# reflow_controller_v2.net
KiCad netlist of a schematic drawn in EAGLE
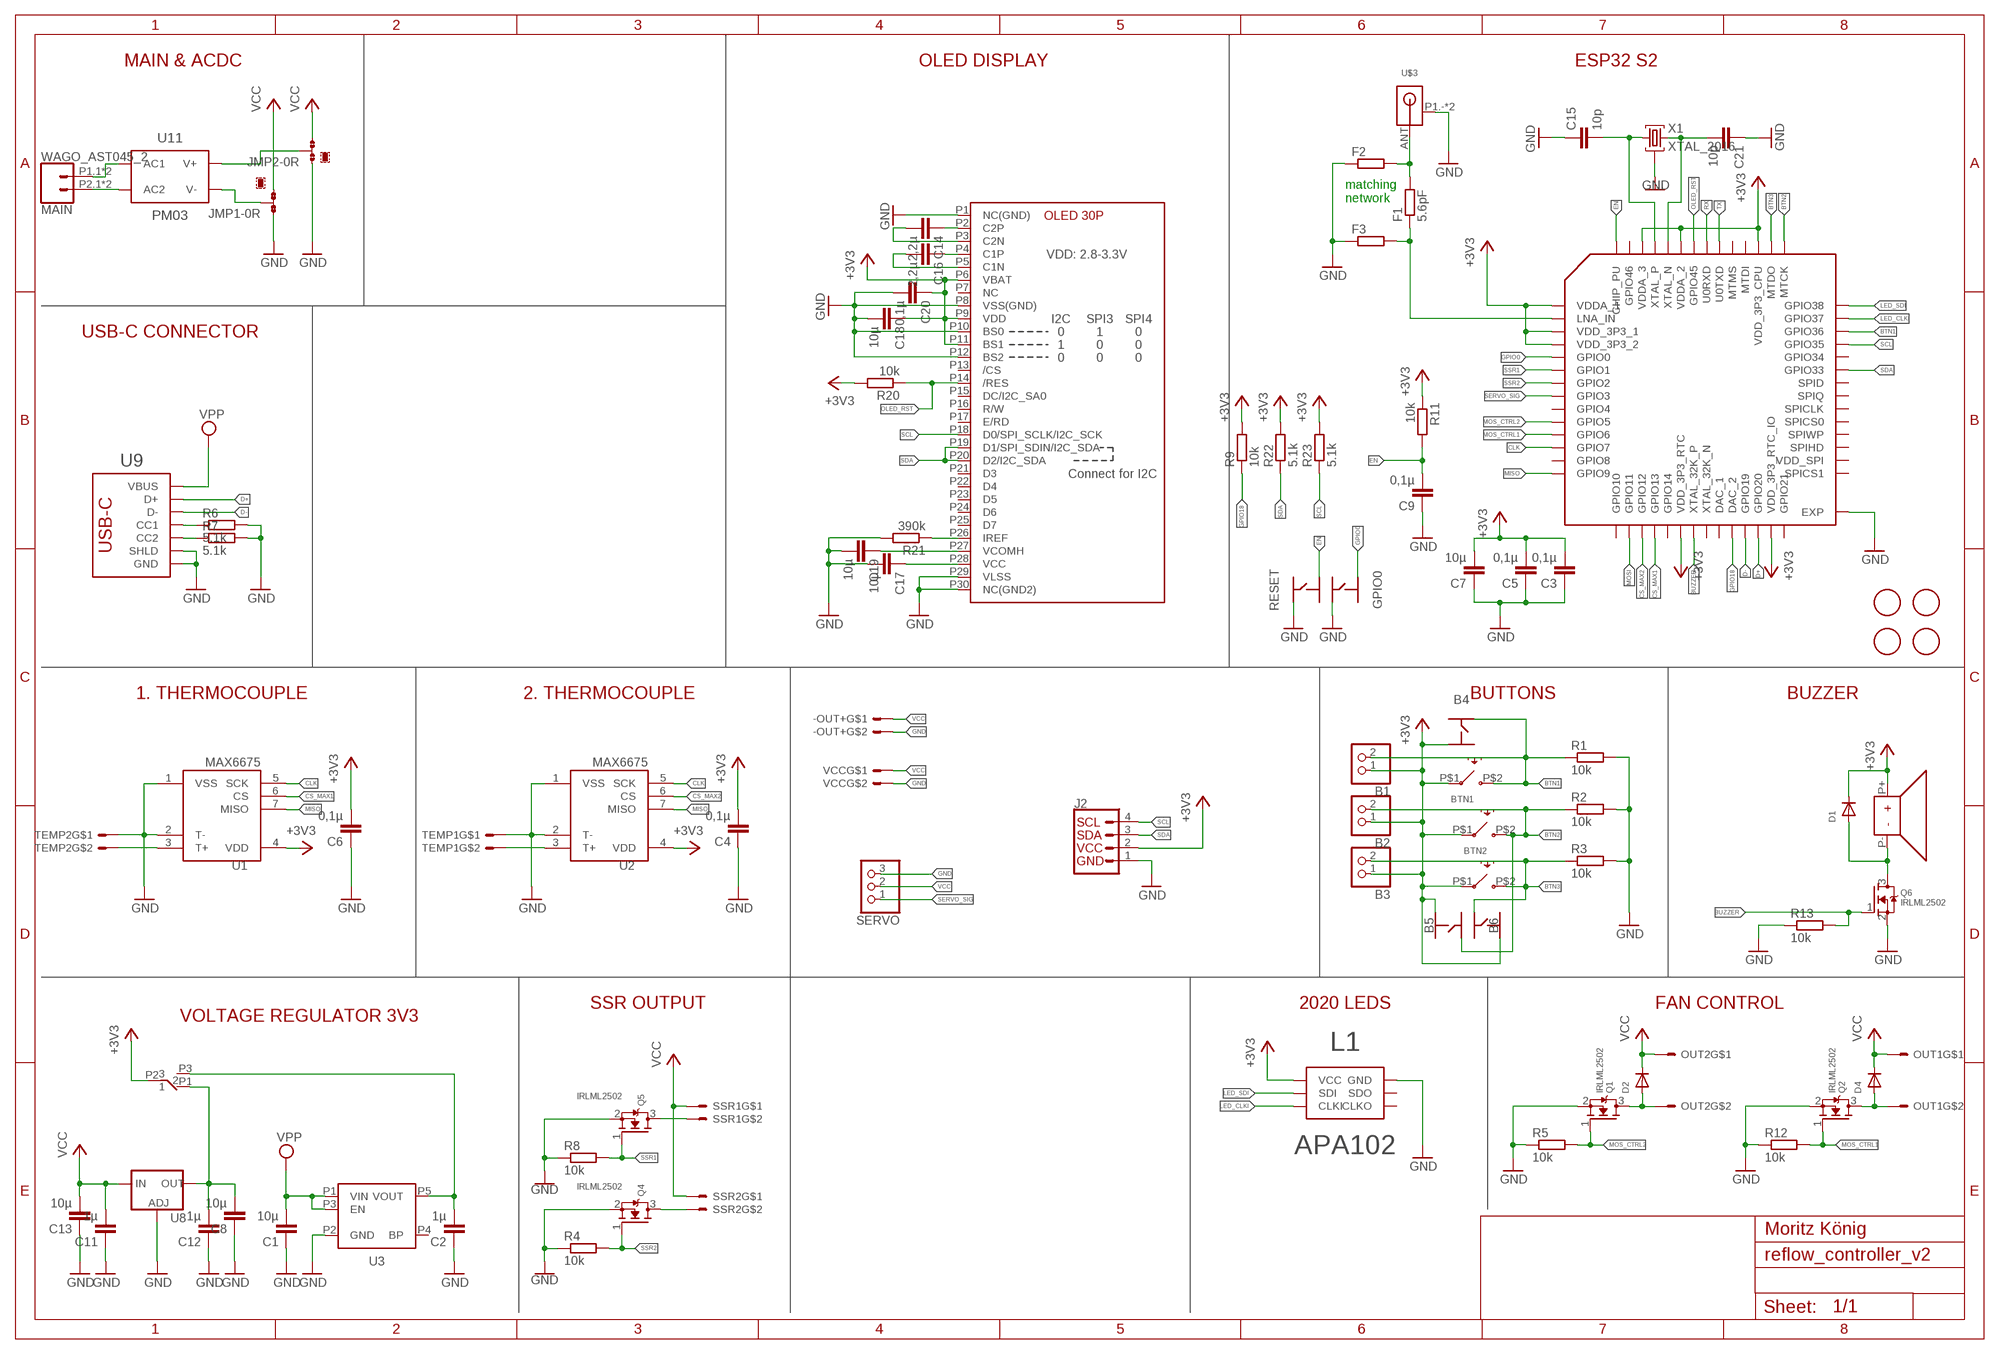
[diagram p0: schematic, sheet 1]

(export (version "E")
  (design (tool "Eeschema 10.0.6"))
  (components
    (comp (ref "-OUT+")
      (value "MOLEX_2MM_2P")
      (footprint "eagle-import:MOLEX_2MM_2P")
      (libsource (lib "eagle-import") (part "MOLEX_2MM_2P"))
    )
    (comp (ref "B1")
      (value "PINHD-1X02_2.00")
      (footprint "eagle-import:1X02M")
      (libsource (lib "eagle-import") (part "PINHD-1X02_2.00"))
    )
    (comp (ref "B2")
      (value "PINHD-1X02_2.00")
      (footprint "eagle-import:1X02M")
      (libsource (lib "eagle-import") (part "PINHD-1X02_2.00"))
    )
    (comp (ref "B3")
      (value "PINHD-1X02_2.00")
      (footprint "eagle-import:1X02M")
      (libsource (lib "eagle-import") (part "PINHD-1X02_2.00"))
    )
    (comp (ref "B4")
      (value "BUTTON_4PIN_TS-1070A")
      (footprint "eagle-import:BUTTON_WHITE_SMD")
      (libsource (lib "eagle-import") (part "BUTTON_4PIN_TS-1070A"))
    )
    (comp (ref "B5")
      (value "BUTTON_4PIN_TS-1070A")
      (footprint "eagle-import:BUTTON_WHITE_SMD")
      (libsource (lib "eagle-import") (part "BUTTON_4PIN_TS-1070A"))
    )
    (comp (ref "B6")
      (value "BUTTON_4PIN_TS-1070A")
      (footprint "eagle-import:BUTTON_WHITE_SMD")
      (libsource (lib "eagle-import") (part "BUTTON_4PIN_TS-1070A"))
    )
    (comp (ref "BTN1")
      (value "BUTTON_6X6_SILICON")
      (footprint "eagle-import:BUTTON_SILICON")
      (libsource (lib "eagle-import") (part "BUTTON_6X6_SILICON"))
    )
    (comp (ref "BTN2")
      (value "BUTTON_6X6_SILICON")
      (footprint "eagle-import:BUTTON_SILICON")
      (libsource (lib "eagle-import") (part "BUTTON_6X6_SILICON"))
    )
    (comp (ref "BTN3")
      (value "BUTTON_6X6_SILICON")
      (footprint "eagle-import:BUTTON_SILICON")
      (libsource (lib "eagle-import") (part "BUTTON_6X6_SILICON"))
    )
    (comp (ref "C1")
      (value "10µ")
      (footprint "eagle-import:C0603")
      (libsource (lib "eagle-import") (part "C-EU_WO_KEEPOUT"))
    )
    (comp (ref "C2")
      (value "1µ")
      (footprint "eagle-import:C0603")
      (libsource (lib "eagle-import") (part "C-EU_WO_KEEPOUT"))
    )
    (comp (ref "C3")
      (value "0,1µ")
      (footprint "eagle-import:C0603")
      (libsource (lib "eagle-import") (part "C-EU_WO_KEEPOUT"))
    )
    (comp (ref "C4")
      (value "0,1µ")
      (footprint "eagle-import:C0603")
      (libsource (lib "eagle-import") (part "C-EUC0603"))
    )
    (comp (ref "C5")
      (value "0,1µ")
      (footprint "eagle-import:C0603")
      (libsource (lib "eagle-import") (part "C-EU_WO_KEEPOUT"))
    )
    (comp (ref "C6")
      (value "0,1µ")
      (footprint "eagle-import:C0603")
      (libsource (lib "eagle-import") (part "C-EUC0603"))
    )
    (comp (ref "C7")
      (value "10µ")
      (footprint "eagle-import:C0603")
      (libsource (lib "eagle-import") (part "C-EU_WO_KEEPOUT"))
    )
    (comp (ref "C8")
      (value "10µ")
      (footprint "eagle-import:C0603")
      (libsource (lib "eagle-import") (part "C-EU_WO_KEEPOUT"))
    )
    (comp (ref "C9")
      (value "0,1µ")
      (footprint "eagle-import:C0603")
      (libsource (lib "eagle-import") (part "C-EU_WO_KEEPOUT"))
    )
    (comp (ref "C11")
      (value "1µ")
      (footprint "eagle-import:C0603")
      (libsource (lib "eagle-import") (part "C-EU_WO_KEEPOUT"))
    )
    (comp (ref "C12")
      (value "1µ")
      (footprint "eagle-import:C0603")
      (libsource (lib "eagle-import") (part "C-EU_WO_KEEPOUT"))
    )
    (comp (ref "C13")
      (value "10µ")
      (footprint "eagle-import:C0603")
      (libsource (lib "eagle-import") (part "C-EU_WO_KEEPOUT"))
    )
    (comp (ref "C14")
      (value "2,2µ")
      (footprint "eagle-import:C0603")
      (libsource (lib "eagle-import") (part "C-EU_WO_KEEPOUT"))
    )
    (comp (ref "C15")
      (value "10p")
      (footprint "eagle-import:C0603")
      (libsource (lib "eagle-import") (part "C-EU_WO_KEEPOUT"))
    )
    (comp (ref "C16")
      (value "2,2µ")
      (footprint "eagle-import:C0603")
      (libsource (lib "eagle-import") (part "C-EU_WO_KEEPOUT"))
    )
    (comp (ref "C17")
      (value "10µ")
      (footprint "eagle-import:C0603")
      (libsource (lib "eagle-import") (part "C-EU_WO_KEEPOUT"))
    )
    (comp (ref "C18")
      (value "10µ")
      (footprint "eagle-import:C0603")
      (libsource (lib "eagle-import") (part "C-EU_WO_KEEPOUT"))
    )
    (comp (ref "C19")
      (value "10µ")
      (footprint "eagle-import:C0603")
      (libsource (lib "eagle-import") (part "C-EU_WO_KEEPOUT"))
    )
    (comp (ref "C20")
      (value "0,1µ")
      (footprint "eagle-import:C0603")
      (libsource (lib "eagle-import") (part "C-EU_WO_KEEPOUT"))
    )
    (comp (ref "C21")
      (value "10p")
      (footprint "eagle-import:C0603")
      (libsource (lib "eagle-import") (part "C-EU_WO_KEEPOUT"))
    )
    (comp (ref "D1")
      (value "DIODESOD-123")
      (footprint "eagle-import:SOD-123")
      (libsource (lib "eagle-import") (part "DIODESOD-123"))
    )
    (comp (ref "D2")
      (value "DIODESOD-123")
      (footprint "eagle-import:SOD-123")
      (libsource (lib "eagle-import") (part "DIODESOD-123"))
    )
    (comp (ref "D4")
      (value "DIODESOD-123")
      (footprint "eagle-import:SOD-123")
      (libsource (lib "eagle-import") (part "DIODESOD-123"))
    )
    (comp (ref "ESP")
      (value "ESP32_S2_QFN56_NEW")
      (footprint "eagle-import:QFN56_7X7")
      (libsource (lib "eagle-import") (part "ESP32_S2_QFN56_NEW"))
    )
    (comp (ref "F1")
      (value "5.6pF")
      (footprint "eagle-import:R0402")
      (libsource (lib "eagle-import") (part "R-EU-0402-WOKEEPOUT"))
    )
    (comp (ref "F2")
      (value "R-EU-0402-WOKEEPOUT")
      (footprint "eagle-import:R0402")
      (libsource (lib "eagle-import") (part "R-EU-0402-WOKEEPOUT"))
    )
    (comp (ref "F3")
      (value "R-EU-0402-WOKEEPOUT")
      (footprint "eagle-import:R0402")
      (libsource (lib "eagle-import") (part "R-EU-0402-WOKEEPOUT"))
    )
    (comp (ref "GPIO0")
      (value "BUTTON_4PIN_TS_1177")
      (footprint "eagle-import:TS-1177-C-B-B")
      (libsource (lib "eagle-import") (part "BUTTON_4PIN_TS_1177"))
    )
    (comp (ref "J2")
      (value "QWIIC_CONNECTORJS-1MM")
      (footprint "eagle-import:1X04_1MM_RA")
      (libsource (lib "eagle-import") (part "QWIIC_CONNECTORJS-1MM"))
    )
    (comp (ref "JMP1")
      (value "0R-JUMPA")
      (footprint "eagle-import:A0R-JMP")
      (libsource (lib "eagle-import") (part "0R-JUMPA"))
    )
    (comp (ref "JMP2")
      (value "0R-JUMPA")
      (footprint "eagle-import:A0R-JMP")
      (libsource (lib "eagle-import") (part "0R-JUMPA"))
    )
    (comp (ref "L1")
      (value "APA102_2020")
      (footprint "eagle-import:APA102_2020")
      (libsource (lib "eagle-import") (part "APA102_2020"))
    )
    (comp (ref "MAIN")
      (value "WAGO_AST045_2")
      (footprint "eagle-import:WAGO_AST045_2")
      (libsource (lib "eagle-import") (part "WAGO_AST045_2"))
    )
    (comp (ref "OUT1")
      (value "MOLEX_2MM_2P")
      (footprint "eagle-import:MOLEX_2MM_2P")
      (libsource (lib "eagle-import") (part "MOLEX_2MM_2P"))
    )
    (comp (ref "OUT2")
      (value "MOLEX_2MM_2P")
      (footprint "eagle-import:MOLEX_2MM_2P")
      (libsource (lib "eagle-import") (part "MOLEX_2MM_2P"))
    )
    (comp (ref "Q1")
      (value "IRLML2502")
      (footprint "eagle-import:SOT23")
      (libsource (lib "eagle-import") (part "IRLML2502"))
    )
    (comp (ref "Q2")
      (value "IRLML2502")
      (footprint "eagle-import:SOT23")
      (libsource (lib "eagle-import") (part "IRLML2502"))
    )
    (comp (ref "Q4")
      (value "IRLML2502")
      (footprint "eagle-import:SOT23")
      (libsource (lib "eagle-import") (part "IRLML2502"))
    )
    (comp (ref "Q5")
      (value "IRLML2502")
      (footprint "eagle-import:SOT23")
      (libsource (lib "eagle-import") (part "IRLML2502"))
    )
    (comp (ref "Q6")
      (value "IRLML2502")
      (footprint "eagle-import:SOT23")
      (libsource (lib "eagle-import") (part "IRLML2502"))
    )
    (comp (ref "R1")
      (value "10k")
      (footprint "eagle-import:R0603")
      (libsource (lib "eagle-import") (part "R-EU_WO_KEEPOUT"))
    )
    (comp (ref "R2")
      (value "10k")
      (footprint "eagle-import:R0603")
      (libsource (lib "eagle-import") (part "R-EU_WO_KEEPOUT"))
    )
    (comp (ref "R3")
      (value "10k")
      (footprint "eagle-import:R0603")
      (libsource (lib "eagle-import") (part "R-EU_WO_KEEPOUT"))
    )
    (comp (ref "R4")
      (value "10k")
      (footprint "eagle-import:R0603")
      (libsource (lib "eagle-import") (part "R-EU_WO_KEEPOUT"))
    )
    (comp (ref "R5")
      (value "10k")
      (footprint "eagle-import:R0603")
      (libsource (lib "eagle-import") (part "R-EU_WO_KEEPOUT"))
    )
    (comp (ref "R6")
      (value "5.1k")
      (footprint "eagle-import:R0603")
      (libsource (lib "eagle-import") (part "R-EU_WO_KEEPOUT"))
    )
    (comp (ref "R7")
      (value "5.1k")
      (footprint "eagle-import:R0603")
      (libsource (lib "eagle-import") (part "R-EU_WO_KEEPOUT"))
    )
    (comp (ref "R8")
      (value "10k")
      (footprint "eagle-import:R0603")
      (libsource (lib "eagle-import") (part "R-EU_WO_KEEPOUT"))
    )
    (comp (ref "R9")
      (value "10k")
      (footprint "eagle-import:R0603")
      (libsource (lib "eagle-import") (part "R-EU_WO_KEEPOUT"))
    )
    (comp (ref "R11")
      (value "10k")
      (footprint "eagle-import:R0603")
      (libsource (lib "eagle-import") (part "R-EU_WO_KEEPOUT"))
    )
    (comp (ref "R12")
      (value "10k")
      (footprint "eagle-import:R0603")
      (libsource (lib "eagle-import") (part "R-EU_WO_KEEPOUT"))
    )
    (comp (ref "R13")
      (value "10k")
      (footprint "eagle-import:R0603")
      (libsource (lib "eagle-import") (part "R-EU_WO_KEEPOUT"))
    )
    (comp (ref "R20")
      (value "10k")
      (footprint "eagle-import:R0603")
      (libsource (lib "eagle-import") (part "R-EU_WO_KEEPOUT"))
    )
    (comp (ref "R21")
      (value "390k")
      (footprint "eagle-import:R0603")
      (libsource (lib "eagle-import") (part "R-EU_WO_KEEPOUT"))
    )
    (comp (ref "R22")
      (value "5.1k")
      (footprint "eagle-import:R0603")
      (libsource (lib "eagle-import") (part "R-EU_WO_KEEPOUT"))
    )
    (comp (ref "R23")
      (value "5.1k")
      (footprint "eagle-import:R0603")
      (libsource (lib "eagle-import") (part "R-EU_WO_KEEPOUT"))
    )
    (comp (ref "RESET")
      (value "BUTTON_4PIN_TS_1177")
      (footprint "eagle-import:TS-1177-C-B-B")
      (libsource (lib "eagle-import") (part "BUTTON_4PIN_TS_1177"))
    )
    (comp (ref "S1")
      (value "SWITCH_MS-22C01-G010")
      (footprint "eagle-import:MS-22C01-G010")
      (libsource (lib "eagle-import") (part "SWITCH_MS-22C01-G010"))
    )
    (comp (ref "SERVO")
      (value "PINHD-1X03_2.54")
      (footprint "eagle-import:1X03")
      (libsource (lib "eagle-import") (part "PINHD-1X03_2.54"))
    )
    (comp (ref "SSR1")
      (value "MOLEX_2MM_2P")
      (footprint "eagle-import:MOLEX_2MM_2P")
      (libsource (lib "eagle-import") (part "MOLEX_2MM_2P"))
    )
    (comp (ref "SSR2")
      (value "MOLEX_2MM_2P")
      (footprint "eagle-import:MOLEX_2MM_2P")
      (libsource (lib "eagle-import") (part "MOLEX_2MM_2P"))
    )
    (comp (ref "TEMP1")
      (value "MOLEX_2MM_2P")
      (footprint "eagle-import:MOLEX_2MM_2P")
      (libsource (lib "eagle-import") (part "MOLEX_2MM_2P"))
    )
    (comp (ref "TEMP2")
      (value "MOLEX_2MM_2P")
      (footprint "eagle-import:MOLEX_2MM_2P")
      (libsource (lib "eagle-import") (part "MOLEX_2MM_2P"))
    )
    (comp (ref "U$1")
      (value "FIDUCIAL")
      (footprint "eagle-import:FIDUCIAL_1MM")
      (libsource (lib "eagle-import") (part "FIDUCIAL"))
    )
    (comp (ref "U$2")
      (value "FIDUCIAL")
      (footprint "eagle-import:FIDUCIAL_1MM")
      (libsource (lib "eagle-import") (part "FIDUCIAL"))
    )
    (comp (ref "U$3")
      (value "UFL_ANT_CONNECTOR")
      (footprint "eagle-import:UFL_ANT_CONNECTOR")
      (libsource (lib "eagle-import") (part "UFL_ANT_CONNECTOR"))
    )
    (comp (ref "U$4")
      (value "FIDUCIAL")
      (footprint "eagle-import:FIDUCIAL_1MM")
      (libsource (lib "eagle-import") (part "FIDUCIAL"))
    )
    (comp (ref "U$5")
      (value "FIDUCIAL")
      (footprint "eagle-import:FIDUCIAL_1MM")
      (libsource (lib "eagle-import") (part "FIDUCIAL"))
    )
    (comp (ref "U1")
      (value "MAX6675")
      (footprint "eagle-import:SO08")
      (libsource (lib "eagle-import") (part "MAX6675"))
    )
    (comp (ref "U2")
      (value "MAX6675")
      (footprint "eagle-import:SO08")
      (libsource (lib "eagle-import") (part "MAX6675"))
    )
    (comp (ref "U3")
      (value "RT9193_SC70-5")
      (footprint "eagle-import:SC-70-5")
      (libsource (lib "eagle-import") (part "RT9193_SC70-5"))
    )
    (comp (ref "U4")
      (value "OLD_096_SSD1306_30P_2B")
      (footprint "eagle-import:OLED_096_30P_B")
      (libsource (lib "eagle-import") (part "OLD_096_SSD1306_30P_2B"))
    )
    (comp (ref "U8")
      (value "V_REG_LM1117SOT223")
      (footprint "eagle-import:SOT223")
      (libsource (lib "eagle-import") (part "V_REG_LM1117SOT223"))
    )
    (comp (ref "U9")
      (value "USB_C_C393939")
      (footprint "eagle-import:USBC_C393939")
      (libsource (lib "eagle-import") (part "USB_C_C393939"))
    )
    (comp (ref "U10")
      (value "MLT-5030-BUZZER")
      (footprint "eagle-import:MLT-5030-BUZZER")
      (libsource (lib "eagle-import") (part "MLT-5030-BUZZER"))
    )
    (comp (ref "U11")
      (value "HILINK_PM03")
      (footprint "eagle-import:HILINK_PM03")
      (libsource (lib "eagle-import") (part "HILINK_PM03"))
    )
    (comp (ref "VCC")
      (value "MOLEX_2MM_2P")
      (footprint "eagle-import:MOLEX_2MM_2P")
      (libsource (lib "eagle-import") (part "MOLEX_2MM_2P"))
    )
    (comp (ref "X1")
      (value "XTAL_2016")
      (footprint "eagle-import:XTYL_2016")
      (libsource (lib "eagle-import") (part "XTAL_2016"))
    )
  )
  (nets
    (net (code "1") (name "+3V3") (class "Default")
      (node (ref "B1") (pin "1") (pinfunction "1_1") (pintype "passive"))
      (node (ref "B2") (pin "1") (pinfunction "1_1") (pintype "passive"))
      (node (ref "B3") (pin "1") (pinfunction "1_1") (pintype "passive"))
      (node (ref "B4") (pin "P$2") (pinfunction "3_P$2") (pintype "bidirectional"))
      (node (ref "B5") (pin "P$2") (pinfunction "3_P$2") (pintype "bidirectional"))
      (node (ref "B6") (pin "P$2") (pinfunction "3_P$2") (pintype "bidirectional"))
      (node (ref "BTN1") (pin "P$1") (pinfunction "P1_P$1") (pintype "bidirectional"))
      (node (ref "BTN2") (pin "P$1") (pinfunction "P1_P$1") (pintype "bidirectional"))
      (node (ref "BTN3") (pin "P$1") (pinfunction "P1_P$1") (pintype "bidirectional"))
      (node (ref "C18") (pin "1") (pinfunction "1_1") (pintype "passive"))
      (node (ref "C20") (pin "1") (pinfunction "1_1") (pintype "passive"))
      (node (ref "C3") (pin "2") (pinfunction "2_2") (pintype "passive"))
      (node (ref "C4") (pin "2") (pinfunction "2_2") (pintype "passive"))
      (node (ref "C5") (pin "2") (pinfunction "2_2") (pintype "passive"))
      (node (ref "C6") (pin "2") (pinfunction "2_2") (pintype "passive"))
      (node (ref "C7") (pin "2") (pinfunction "2_2") (pintype "passive"))
      (node (ref "D1") (pin "C") (pinfunction "C_C") (pintype "passive"))
      (node (ref "ESP") (pin "1") (pinfunction "VDDA_1_1") (pintype "bidirectional"))
      (node (ref "ESP") (pin "20") (pinfunction "VDD_3P3_RTC_20") (pintype "bidirectional"))
      (node (ref "ESP") (pin "27") (pinfunction "VDD_3P3_RTC_IO_27") (pintype "bidirectional"))
      (node (ref "ESP") (pin "3") (pinfunction "VDD_3P3_1_3") (pintype "bidirectional"))
      (node (ref "ESP") (pin "4") (pinfunction "VDD_3P3_2_4") (pintype "bidirectional"))
      (node (ref "ESP") (pin "45") (pinfunction "VDD_3P3_CPU_45") (pintype "bidirectional"))
      (node (ref "ESP") (pin "51") (pinfunction "VDDA_2_51") (pintype "bidirectional"))
      (node (ref "ESP") (pin "54") (pinfunction "VDDA_3_54") (pintype "bidirectional"))
      (node (ref "J2") (pin "2") (pinfunction "VCC_2") (pintype "power_in"))
      (node (ref "L1") (pin "P1") (pinfunction "VCC_P1") (pintype "bidirectional"))
      (node (ref "L1") (pin "P1.1") (pinfunction "VCC_P1.1") (pintype "bidirectional"))
      (node (ref "R11") (pin "1") (pinfunction "1_1") (pintype "passive"))
      (node (ref "R20") (pin "2") (pinfunction "2_2") (pintype "passive"))
      (node (ref "R22") (pin "2") (pinfunction "2_2") (pintype "passive"))
      (node (ref "R23") (pin "2") (pinfunction "2_2") (pintype "passive"))
      (node (ref "R9") (pin "2") (pinfunction "2_2") (pintype "passive"))
      (node (ref "S1") (pin "P2") (pinfunction "2_P2") (pintype "bidirectional"))
      (node (ref "U1") (pin "4") (pinfunction "VDD_4") (pintype "bidirectional"))
      (node (ref "U10") (pin "P+") (pinfunction "P+_P+") (pintype "bidirectional"))
      (node (ref "U2") (pin "4") (pinfunction "VDD_4") (pintype "bidirectional"))
      (node (ref "U4") (pin "P11") (pinfunction "BS1_P11") (pintype "bidirectional"))
      (node (ref "U4") (pin "P6") (pinfunction "VBAT_P6") (pintype "bidirectional"))
      (node (ref "U4") (pin "P9") (pinfunction "VDD_P9") (pintype "bidirectional"))
    )
    (net (code "2") (name "BTN1") (class "Default")
      (node (ref "B1") (pin "2") (pinfunction "2_2") (pintype "passive"))
      (node (ref "B4") (pin "P$4") (pinfunction "2_P$4") (pintype "bidirectional"))
      (node (ref "BTN1") (pin "P$2") (pinfunction "P2_P$2") (pintype "bidirectional"))
      (node (ref "ESP") (pin "40") (pinfunction "GPIO36_40") (pintype "bidirectional"))
      (node (ref "R1") (pin "1") (pinfunction "1_1") (pintype "passive"))
    )
    (net (code "3") (name "BTN2") (class "Default")
      (node (ref "B2") (pin "2") (pinfunction "2_2") (pintype "passive"))
      (node (ref "B5") (pin "P$4") (pinfunction "2_P$4") (pintype "bidirectional"))
      (node (ref "BTN2") (pin "P$2") (pinfunction "P2_P$2") (pintype "bidirectional"))
      (node (ref "ESP") (pin "43") (pinfunction "MTCK_43") (pintype "bidirectional"))
      (node (ref "R2") (pin "1") (pinfunction "1_1") (pintype "passive"))
    )
    (net (code "4") (name "BTN3") (class "Default")
      (node (ref "B3") (pin "2") (pinfunction "2_2") (pintype "passive"))
      (node (ref "B6") (pin "P$4") (pinfunction "2_P$4") (pintype "bidirectional"))
      (node (ref "BTN3") (pin "P$2") (pinfunction "P2_P$2") (pintype "bidirectional"))
      (node (ref "ESP") (pin "44") (pinfunction "MTDO_44") (pintype "bidirectional"))
      (node (ref "R3") (pin "1") (pinfunction "1_1") (pintype "passive"))
    )
    (net (code "5") (name "BUZZER") (class "Default")
      (node (ref "ESP") (pin "21") (pinfunction "XTAL_32K_P_21") (pintype "bidirectional"))
      (node (ref "Q6") (pin "1") (pinfunction "G_1") (pintype "bidirectional"))
      (node (ref "R13") (pin "2") (pinfunction "2_2") (pintype "passive"))
    )
    (net (code "6") (name "CLK") (class "Default")
      (node (ref "ESP") (pin "12") (pinfunction "GPIO7_12") (pintype "bidirectional"))
      (node (ref "U1") (pin "5") (pinfunction "SCK_5") (pintype "bidirectional"))
      (node (ref "U2") (pin "5") (pinfunction "SCK_5") (pintype "bidirectional"))
    )
    (net (code "7") (name "CS_MAX1") (class "Default")
      (node (ref "ESP") (pin "18") (pinfunction "GPIO13_18") (pintype "bidirectional"))
      (node (ref "U1") (pin "6") (pinfunction "CS_6") (pintype "bidirectional"))
    )
    (net (code "8") (name "CS_MAX2") (class "Default")
      (node (ref "ESP") (pin "17") (pinfunction "GPIO12_17") (pintype "bidirectional"))
      (node (ref "U2") (pin "6") (pinfunction "CS_6") (pintype "bidirectional"))
    )
    (net (code "9") (name "D+") (class "Default")
      (node (ref "ESP") (pin "26") (pinfunction "GPIO20_26") (pintype "bidirectional"))
      (node (ref "U9") (pin "A6") (pinfunction "D+_A6") (pintype "bidirectional"))
      (node (ref "U9") (pin "B6") (pinfunction "D+_B6") (pintype "bidirectional"))
    )
    (net (code "10") (name "D-") (class "Default")
      (node (ref "ESP") (pin "25") (pinfunction "GPIO19_25") (pintype "bidirectional"))
      (node (ref "U9") (pin "A7") (pinfunction "D-_A7") (pintype "bidirectional"))
      (node (ref "U9") (pin "B7") (pinfunction "D-_B7") (pintype "bidirectional"))
    )
    (net (code "11") (name "EN") (class "Default")
      (node (ref "C9") (pin "2") (pinfunction "2_2") (pintype "passive"))
      (node (ref "ESP") (pin "56") (pinfunction "CHIP_PU_56") (pintype "bidirectional"))
      (node (ref "R11") (pin "2") (pinfunction "2_2") (pintype "passive"))
      (node (ref "RESET") (pin "P4") (pinfunction "4_P4") (pintype "bidirectional"))
    )
    (net (code "12") (name "GND") (class "Default")
      (node (ref "-OUT+") (pin "2") (pinfunction "S_2") (pintype "passive"))
      (node (ref "C1") (pin "1") (pinfunction "1_1") (pintype "passive"))
      (node (ref "C11") (pin "1") (pinfunction "1_1") (pintype "passive"))
      (node (ref "C12") (pin "1") (pinfunction "1_1") (pintype "passive"))
      (node (ref "C13") (pin "1") (pinfunction "1_1") (pintype "passive"))
      (node (ref "C15") (pin "1") (pinfunction "1_1") (pintype "passive"))
      (node (ref "C17") (pin "2") (pinfunction "2_2") (pintype "passive"))
      (node (ref "C18") (pin "2") (pinfunction "2_2") (pintype "passive"))
      (node (ref "C19") (pin "2") (pinfunction "2_2") (pintype "passive"))
      (node (ref "C2") (pin "1") (pinfunction "1_1") (pintype "passive"))
      (node (ref "C20") (pin "2") (pinfunction "2_2") (pintype "passive"))
      (node (ref "C21") (pin "1") (pinfunction "1_1") (pintype "passive"))
      (node (ref "C3") (pin "1") (pinfunction "1_1") (pintype "passive"))
      (node (ref "C4") (pin "1") (pinfunction "1_1") (pintype "passive"))
      (node (ref "C5") (pin "1") (pinfunction "1_1") (pintype "passive"))
      (node (ref "C6") (pin "1") (pinfunction "1_1") (pintype "passive"))
      (node (ref "C7") (pin "1") (pinfunction "1_1") (pintype "passive"))
      (node (ref "C8") (pin "1") (pinfunction "1_1") (pintype "passive"))
      (node (ref "C9") (pin "1") (pinfunction "1_1") (pintype "passive"))
      (node (ref "ESP") (pin "57") (pinfunction "EXP_57") (pintype "bidirectional"))
      (node (ref "F2") (pin "1") (pinfunction "1_1") (pintype "passive"))
      (node (ref "F3") (pin "1") (pinfunction "1_1") (pintype "passive"))
      (node (ref "GPIO0") (pin "P1") (pinfunction "1_P1") (pintype "bidirectional"))
      (node (ref "J2") (pin "1") (pinfunction "GND_1") (pintype "power_in"))
      (node (ref "JMP1") (pin "1") (pinfunction "1_1") (pintype "passive"))
      (node (ref "JMP2") (pin "1") (pinfunction "1_1") (pintype "passive"))
      (node (ref "L1") (pin "P6") (pinfunction "GND_P6") (pintype "bidirectional"))
      (node (ref "L1") (pin "P6.1") (pinfunction "GND_P6.1") (pintype "bidirectional"))
      (node (ref "Q1") (pin "2") (pinfunction "S_2") (pintype "bidirectional"))
      (node (ref "Q2") (pin "2") (pinfunction "S_2") (pintype "bidirectional"))
      (node (ref "Q4") (pin "2") (pinfunction "S_2") (pintype "bidirectional"))
      (node (ref "Q5") (pin "2") (pinfunction "S_2") (pintype "bidirectional"))
      (node (ref "Q6") (pin "2") (pinfunction "S_2") (pintype "bidirectional"))
      (node (ref "R1") (pin "2") (pinfunction "2_2") (pintype "passive"))
      (node (ref "R12") (pin "1") (pinfunction "1_1") (pintype "passive"))
      (node (ref "R13") (pin "1") (pinfunction "1_1") (pintype "passive"))
      (node (ref "R2") (pin "2") (pinfunction "2_2") (pintype "passive"))
      (node (ref "R21") (pin "2") (pinfunction "2_2") (pintype "passive"))
      (node (ref "R3") (pin "2") (pinfunction "2_2") (pintype "passive"))
      (node (ref "R4") (pin "1") (pinfunction "1_1") (pintype "passive"))
      (node (ref "R5") (pin "1") (pinfunction "1_1") (pintype "passive"))
      (node (ref "R6") (pin "2") (pinfunction "2_2") (pintype "passive"))
      (node (ref "R7") (pin "2") (pinfunction "2_2") (pintype "passive"))
      (node (ref "R8") (pin "1") (pinfunction "1_1") (pintype "passive"))
      (node (ref "RESET") (pin "P1") (pinfunction "1_P1") (pintype "bidirectional"))
      (node (ref "SERVO") (pin "3") (pinfunction "3_3") (pintype "passive"))
      (node (ref "TEMP1") (pin "1") (pinfunction "S_1") (pintype "passive"))
      (node (ref "TEMP2") (pin "1") (pinfunction "S_1") (pintype "passive"))
      (node (ref "U$3") (pin "P1.-") (pinfunction "GND_P1.-") (pintype "bidirectional"))
      (node (ref "U$3") (pin "P2.-") (pinfunction "GND_P2.-") (pintype "bidirectional"))
      (node (ref "U1") (pin "1") (pinfunction "VSS_1") (pintype "bidirectional"))
      (node (ref "U1") (pin "2") (pinfunction "T-_2") (pintype "bidirectional"))
      (node (ref "U2") (pin "1") (pinfunction "VSS_1") (pintype "bidirectional"))
      (node (ref "U2") (pin "2") (pinfunction "T-_2") (pintype "bidirectional"))
      (node (ref "U3") (pin "P2") (pinfunction "GND_P2") (pintype "bidirectional"))
      (node (ref "U4") (pin "P1") (pinfunction "NC(GND)_P1") (pintype "bidirectional"))
      (node (ref "U4") (pin "P10") (pinfunction "BS0_P10") (pintype "bidirectional"))
      (node (ref "U4") (pin "P12") (pinfunction "BS2_P12") (pintype "bidirectional"))
      (node (ref "U4") (pin "P29") (pinfunction "VLSS_P29") (pintype "bidirectional"))
      (node (ref "U4") (pin "P30") (pinfunction "NC(GND2)_P30") (pintype "bidirectional"))
      (node (ref "U4") (pin "P8") (pinfunction "VSS(GND)_P8") (pintype "bidirectional"))
      (node (ref "U8") (pin "1") (pinfunction "ADJ_1") (pintype "input"))
      (node (ref "U9") (pin "A1B12") (pinfunction "GND_A1B12") (pintype "bidirectional"))
      (node (ref "U9") (pin "B1A12") (pinfunction "GND_B1A12") (pintype "bidirectional"))
      (node (ref "U9") (pin "S1") (pinfunction "SHLD_S1") (pintype "bidirectional"))
      (node (ref "U9") (pin "S2") (pinfunction "SHLD_S2") (pintype "bidirectional"))
      (node (ref "U9") (pin "S3") (pinfunction "SHLD_S3") (pintype "bidirectional"))
      (node (ref "U9") (pin "S4") (pinfunction "SHLD_S4") (pintype "bidirectional"))
      (node (ref "VCC") (pin "2") (pinfunction "S_2") (pintype "passive"))
      (node (ref "X1") (pin "P2") (pinfunction "G_P2") (pintype "passive"))
      (node (ref "X1") (pin "P4") (pinfunction "G_P4") (pintype "passive"))
    )
    (net (code "13") (name "GPIO0") (class "Default")
      (node (ref "ESP") (pin "5") (pinfunction "GPIO0_5") (pintype "bidirectional"))
      (node (ref "GPIO0") (pin "P4") (pinfunction "4_P4") (pintype "bidirectional"))
    )
    (net (code "14") (name "GPIO18") (class "Default")
      (node (ref "ESP") (pin "24") (pinfunction "DAC_2_24") (pintype "bidirectional"))
      (node (ref "R9") (pin "1") (pinfunction "1_1") (pintype "passive"))
    )
    (net (code "15") (name "LED_CLKI") (class "Default")
      (node (ref "ESP") (pin "41") (pinfunction "GPIO37_41") (pintype "bidirectional"))
      (node (ref "L1") (pin "P5") (pinfunction "CLKI_P5") (pintype "bidirectional"))
    )
    (net (code "16") (name "LED_SDI") (class "Default")
      (node (ref "ESP") (pin "42") (pinfunction "GPIO38_42") (pintype "bidirectional"))
      (node (ref "L1") (pin "P4") (pinfunction "SDI_P4") (pintype "bidirectional"))
    )
    (net (code "17") (name "MISO") (class "Default")
      (node (ref "ESP") (pin "14") (pinfunction "GPIO9_14") (pintype "bidirectional"))
      (node (ref "U1") (pin "7") (pinfunction "MISO_7") (pintype "bidirectional"))
      (node (ref "U2") (pin "7") (pinfunction "MISO_7") (pintype "bidirectional"))
    )
    (net (code "18") (name "MOSI") (class "Default")
      (node (ref "ESP") (pin "16") (pinfunction "GPIO11_16") (pintype "bidirectional"))
    )
    (net (code "19") (name "MOS_CTRL1") (class "Default")
      (node (ref "ESP") (pin "11") (pinfunction "GPIO6_11") (pintype "bidirectional"))
      (node (ref "Q2") (pin "1") (pinfunction "G_1") (pintype "bidirectional"))
      (node (ref "R12") (pin "2") (pinfunction "2_2") (pintype "passive"))
    )
    (net (code "20") (name "MOS_CTRL2") (class "Default")
      (node (ref "ESP") (pin "10") (pinfunction "GPIO5_10") (pintype "bidirectional"))
      (node (ref "Q1") (pin "1") (pinfunction "G_1") (pintype "bidirectional"))
      (node (ref "R5") (pin "2") (pinfunction "2_2") (pintype "passive"))
    )
    (net (code "21") (name "Net-(ESP-LNA_IN)") (class "Default")
      (node (ref "ESP") (pin "2") (pinfunction "LNA_IN_2") (pintype "bidirectional"))
      (node (ref "F1") (pin "1") (pinfunction "1_1") (pintype "passive"))
      (node (ref "F3") (pin "2") (pinfunction "2_2") (pintype "passive"))
    )
    (net (code "22") (name "Net-(ESP-XTAL_N)") (class "Default")
      (node (ref "C21") (pin "2") (pinfunction "2_2") (pintype "passive"))
      (node (ref "ESP") (pin "52") (pinfunction "XTAL_N_52") (pintype "bidirectional"))
      (node (ref "X1") (pin "P3") (pinfunction "2_P3") (pintype "passive"))
    )
    (net (code "23") (name "Net-(ESP-XTAL_P)") (class "Default")
      (node (ref "C15") (pin "2") (pinfunction "2_2") (pintype "passive"))
      (node (ref "ESP") (pin "53") (pinfunction "XTAL_P_53") (pintype "bidirectional"))
      (node (ref "X1") (pin "P1") (pinfunction "1_P1") (pintype "passive"))
    )
    (net (code "24") (name "Net-(F1-Pad2)") (class "Default")
      (node (ref "F1") (pin "2") (pinfunction "2_2") (pintype "passive"))
      (node (ref "F2") (pin "2") (pinfunction "2_2") (pintype "passive"))
      (node (ref "U$3") (pin "ANT") (pinfunction "ANT_ANT") (pintype "bidirectional"))
    )
    (net (code "25") (name "Net-(JMP1-Pad2)") (class "Default")
      (node (ref "JMP1") (pin "2") (pinfunction "2_2") (pintype "passive"))
      (node (ref "U11") (pin "V-") (pinfunction "V-_V-") (pintype "bidirectional"))
    )
    (net (code "26") (name "Net-(JMP2-Pad2)") (class "Default")
      (node (ref "JMP2") (pin "2") (pinfunction "2_2") (pintype "passive"))
      (node (ref "U11") (pin "V+") (pinfunction "V+_V+") (pintype "bidirectional"))
    )
    (net (code "27") (name "Net-(MAIN-1-PadP1.1)") (class "Default")
      (node (ref "MAIN") (pin "P1.1") (pinfunction "1_P1.1") (pintype "passive"))
      (node (ref "MAIN") (pin "P1.2") (pinfunction "1_P1.2") (pintype "passive"))
      (node (ref "U11") (pin "AC1") (pinfunction "AC1_AC1") (pintype "bidirectional"))
    )
    (net (code "28") (name "Net-(MAIN-2-PadP2.1)") (class "Default")
      (node (ref "MAIN") (pin "P2.1") (pinfunction "2_P2.1") (pintype "passive"))
      (node (ref "MAIN") (pin "P2.2") (pinfunction "2_P2.2") (pintype "passive"))
      (node (ref "U11") (pin "AC2") (pinfunction "AC2_AC2") (pintype "bidirectional"))
    )
    (net (code "29") (name "Net-(OUT1B-S)") (class "Default")
      (node (ref "D4") (pin "A") (pinfunction "A_A") (pintype "passive"))
      (node (ref "OUT1") (pin "2") (pinfunction "S_2") (pintype "passive"))
      (node (ref "Q2") (pin "3") (pinfunction "D_3") (pintype "bidirectional"))
    )
    (net (code "30") (name "Net-(OUT2B-S)") (class "Default")
      (node (ref "D2") (pin "A") (pinfunction "A_A") (pintype "passive"))
      (node (ref "OUT2") (pin "2") (pinfunction "S_2") (pintype "passive"))
      (node (ref "Q1") (pin "3") (pinfunction "D_3") (pintype "bidirectional"))
    )
    (net (code "31") (name "Net-(Q4-D)") (class "Default")
      (node (ref "Q4") (pin "3") (pinfunction "D_3") (pintype "bidirectional"))
      (node (ref "SSR2") (pin "2") (pinfunction "S_2") (pintype "passive"))
    )
    (net (code "32") (name "Net-(Q5-D)") (class "Default")
      (node (ref "Q5") (pin "3") (pinfunction "D_3") (pintype "bidirectional"))
      (node (ref "SSR1") (pin "2") (pinfunction "S_2") (pintype "passive"))
    )
    (net (code "33") (name "Net-(Q6-D)") (class "Default")
      (node (ref "D1") (pin "A") (pinfunction "A_A") (pintype "passive"))
      (node (ref "Q6") (pin "3") (pinfunction "D_3") (pintype "bidirectional"))
      (node (ref "U10") (pin "P-") (pinfunction "P-_P-") (pintype "bidirectional"))
    )
    (net (code "34") (name "Net-(S1-1)") (class "Default")
      (node (ref "C12") (pin "2") (pinfunction "2_2") (pintype "passive"))
      (node (ref "C8") (pin "2") (pinfunction "2_2") (pintype "passive"))
      (node (ref "S1") (pin "P1") (pinfunction "1_P1") (pintype "bidirectional"))
      (node (ref "U8") (pin "2") (pinfunction "OUT_2") (pintype "output"))
      (node (ref "U8") (pin "4") (pinfunction "OUT_4") (pintype "output"))
    )
    (net (code "35") (name "Net-(S1-3)") (class "Default")
      (node (ref "C2") (pin "2") (pinfunction "2_2") (pintype "passive"))
      (node (ref "S1") (pin "P3") (pinfunction "3_P3") (pintype "bidirectional"))
      (node (ref "U3") (pin "P5") (pinfunction "VOUT_P5") (pintype "bidirectional"))
    )
    (net (code "36") (name "Net-(TEMP1B-S)") (class "Default")
      (node (ref "TEMP1") (pin "2") (pinfunction "S_2") (pintype "passive"))
      (node (ref "U2") (pin "3") (pinfunction "T+_3") (pintype "bidirectional"))
    )
    (net (code "37") (name "Net-(TEMP2B-S)") (class "Default")
      (node (ref "TEMP2") (pin "2") (pinfunction "S_2") (pintype "passive"))
      (node (ref "U1") (pin "3") (pinfunction "T+_3") (pintype "bidirectional"))
    )
    (net (code "38") (name "Net-(U4-C1N)") (class "Default")
      (node (ref "C16") (pin "2") (pinfunction "2_2") (pintype "passive"))
      (node (ref "U4") (pin "P5") (pinfunction "C1N_P5") (pintype "bidirectional"))
    )
    (net (code "39") (name "Net-(U4-C1P)") (class "Default")
      (node (ref "C16") (pin "1") (pinfunction "1_1") (pintype "passive"))
      (node (ref "U4") (pin "P4") (pinfunction "C1P_P4") (pintype "bidirectional"))
    )
    (net (code "40") (name "Net-(U4-C2N)") (class "Default")
      (node (ref "C14") (pin "2") (pinfunction "2_2") (pintype "passive"))
      (node (ref "U4") (pin "P3") (pinfunction "C2N_P3") (pintype "bidirectional"))
    )
    (net (code "41") (name "Net-(U4-C2P)") (class "Default")
      (node (ref "C14") (pin "1") (pinfunction "1_1") (pintype "passive"))
      (node (ref "U4") (pin "P2") (pinfunction "C2P_P2") (pintype "bidirectional"))
    )
    (net (code "42") (name "Net-(U4-IREF)") (class "Default")
      (node (ref "R21") (pin "1") (pinfunction "1_1") (pintype "passive"))
      (node (ref "U4") (pin "P26") (pinfunction "IREF_P26") (pintype "bidirectional"))
    )
    (net (code "43") (name "Net-(U4-VCC)") (class "Default")
      (node (ref "C17") (pin "1") (pinfunction "1_1") (pintype "passive"))
      (node (ref "U4") (pin "P28") (pinfunction "VCC_P28") (pintype "bidirectional"))
    )
    (net (code "44") (name "Net-(U4-VCOMH)") (class "Default")
      (node (ref "C19") (pin "1") (pinfunction "1_1") (pintype "passive"))
      (node (ref "U4") (pin "P27") (pinfunction "VCOMH_P27") (pintype "bidirectional"))
    )
    (net (code "45") (name "Net-(U9-CC1)") (class "Default")
      (node (ref "R6") (pin "1") (pinfunction "1_1") (pintype "passive"))
      (node (ref "U9") (pin "A5") (pinfunction "CC1_A5") (pintype "bidirectional"))
    )
    (net (code "46") (name "Net-(U9-CC2)") (class "Default")
      (node (ref "R7") (pin "1") (pinfunction "1_1") (pintype "passive"))
      (node (ref "U9") (pin "B5") (pinfunction "CC2_B5") (pintype "bidirectional"))
    )
    (net (code "47") (name "OLED_RST") (class "Default")
      (node (ref "ESP") (pin "50") (pinfunction "GPIO45_50") (pintype "bidirectional"))
      (node (ref "R20") (pin "1") (pinfunction "1_1") (pintype "passive"))
      (node (ref "U4") (pin "P14") (pinfunction "/RES_P14") (pintype "bidirectional"))
    )
    (net (code "48") (name "RX") (class "Default")
      (node (ref "ESP") (pin "49") (pinfunction "U0RXD_49") (pintype "bidirectional"))
    )
    (net (code "49") (name "SCL") (class "Default")
      (node (ref "ESP") (pin "39") (pinfunction "GPIO35_39") (pintype "bidirectional"))
      (node (ref "J2") (pin "4") (pinfunction "SCL_4") (pintype "passive"))
      (node (ref "R23") (pin "1") (pinfunction "1_1") (pintype "passive"))
      (node (ref "U4") (pin "P18") (pinfunction "D0/SPI_SCLK/I2C_SCK_P18") (pintype "bidirectional"))
    )
    (net (code "50") (name "SDA") (class "Default")
      (node (ref "ESP") (pin "37") (pinfunction "GPIO33_37") (pintype "bidirectional"))
      (node (ref "J2") (pin "3") (pinfunction "SDA_3") (pintype "passive"))
      (node (ref "R22") (pin "1") (pinfunction "1_1") (pintype "passive"))
      (node (ref "U4") (pin "P19") (pinfunction "D1/SPI_SDIN/I2C_SDA_P19") (pintype "bidirectional"))
      (node (ref "U4") (pin "P20") (pinfunction "D2/I2C_SDA_P20") (pintype "bidirectional"))
    )
    (net (code "51") (name "SERVO_SIG") (class "Default")
      (node (ref "ESP") (pin "8") (pinfunction "GPIO3_8") (pintype "bidirectional"))
      (node (ref "SERVO") (pin "1") (pinfunction "1_1") (pintype "passive"))
    )
    (net (code "52") (name "SSR1") (class "Default")
      (node (ref "ESP") (pin "6") (pinfunction "GPIO1_6") (pintype "bidirectional"))
      (node (ref "Q5") (pin "1") (pinfunction "G_1") (pintype "bidirectional"))
      (node (ref "R8") (pin "2") (pinfunction "2_2") (pintype "passive"))
    )
    (net (code "53") (name "SSR2") (class "Default")
      (node (ref "ESP") (pin "7") (pinfunction "GPIO2_7") (pintype "bidirectional"))
      (node (ref "Q4") (pin "1") (pinfunction "G_1") (pintype "bidirectional"))
      (node (ref "R4") (pin "2") (pinfunction "2_2") (pintype "passive"))
    )
    (net (code "54") (name "TX") (class "Default")
      (node (ref "ESP") (pin "48") (pinfunction "U0TXD_48") (pintype "bidirectional"))
    )
    (net (code "55") (name "VCC") (class "Default")
      (node (ref "-OUT+") (pin "1") (pinfunction "S_1") (pintype "passive"))
      (node (ref "C11") (pin "2") (pinfunction "2_2") (pintype "passive"))
      (node (ref "C13") (pin "2") (pinfunction "2_2") (pintype "passive"))
      (node (ref "D2") (pin "C") (pinfunction "C_C") (pintype "passive"))
      (node (ref "D4") (pin "C") (pinfunction "C_C") (pintype "passive"))
      (node (ref "JMP1") (pin "3") (pinfunction "3_3") (pintype "passive"))
      (node (ref "JMP2") (pin "3") (pinfunction "3_3") (pintype "passive"))
      (node (ref "OUT1") (pin "1") (pinfunction "S_1") (pintype "passive"))
      (node (ref "OUT2") (pin "1") (pinfunction "S_1") (pintype "passive"))
      (node (ref "SERVO") (pin "2") (pinfunction "2_2") (pintype "passive"))
      (node (ref "SSR1") (pin "1") (pinfunction "S_1") (pintype "passive"))
      (node (ref "SSR2") (pin "1") (pinfunction "S_1") (pintype "passive"))
      (node (ref "U8") (pin "3") (pinfunction "IN_3") (pintype "input"))
      (node (ref "VCC") (pin "1") (pinfunction "S_1") (pintype "passive"))
    )
    (net (code "56") (name "VPP") (class "Default")
      (node (ref "C1") (pin "2") (pinfunction "2_2") (pintype "passive"))
      (node (ref "U3") (pin "P1") (pinfunction "VIN_P1") (pintype "bidirectional"))
      (node (ref "U3") (pin "P3") (pinfunction "EN_P3") (pintype "bidirectional"))
      (node (ref "U9") (pin "A4B9") (pinfunction "VBUS_A4B9") (pintype "bidirectional"))
      (node (ref "U9") (pin "B4A9") (pinfunction "VBUS_B4A9") (pintype "bidirectional"))
    )
    (net (code "57") (name "unconnected-(B4-1-PadP$1)") (class "Default")
      (node (ref "B4") (pin "P$1") (pinfunction "1_P$1") (pintype "bidirectional"))
    )
    (net (code "58") (name "unconnected-(B4-4-PadP$3)") (class "Default")
      (node (ref "B4") (pin "P$3") (pinfunction "4_P$3") (pintype "bidirectional"))
    )
    (net (code "59") (name "unconnected-(B5-1-PadP$1)") (class "Default")
      (node (ref "B5") (pin "P$1") (pinfunction "1_P$1") (pintype "bidirectional"))
    )
    (net (code "60") (name "unconnected-(B5-4-PadP$3)") (class "Default")
      (node (ref "B5") (pin "P$3") (pinfunction "4_P$3") (pintype "bidirectional"))
    )
    (net (code "61") (name "unconnected-(B6-1-PadP$1)") (class "Default")
      (node (ref "B6") (pin "P$1") (pinfunction "1_P$1") (pintype "bidirectional"))
    )
    (net (code "62") (name "unconnected-(B6-4-PadP$3)") (class "Default")
      (node (ref "B6") (pin "P$3") (pinfunction "4_P$3") (pintype "bidirectional"))
    )
    (net (code "63") (name "unconnected-(ESP-DAC_1-Pad23)") (class "Default")
      (node (ref "ESP") (pin "23") (pinfunction "DAC_1_23") (pintype "bidirectional"))
    )
    (net (code "64") (name "unconnected-(ESP-GPIO4-Pad9)") (class "Default")
      (node (ref "ESP") (pin "9") (pinfunction "GPIO4_9") (pintype "bidirectional"))
    )
    (net (code "65") (name "unconnected-(ESP-GPIO8-Pad13)") (class "Default")
      (node (ref "ESP") (pin "13") (pinfunction "GPIO8_13") (pintype "bidirectional"))
    )
    (net (code "66") (name "unconnected-(ESP-GPIO10-Pad15)") (class "Default")
      (node (ref "ESP") (pin "15") (pinfunction "GPIO10_15") (pintype "bidirectional"))
    )
    (net (code "67") (name "unconnected-(ESP-GPIO14-Pad19)") (class "Default")
      (node (ref "ESP") (pin "19") (pinfunction "GPIO14_19") (pintype "bidirectional"))
    )
    (net (code "68") (name "unconnected-(ESP-GPIO21-Pad28)") (class "Default")
      (node (ref "ESP") (pin "28") (pinfunction "GPIO21_28") (pintype "bidirectional"))
    )
    (net (code "69") (name "unconnected-(ESP-GPIO34-Pad38)") (class "Default")
      (node (ref "ESP") (pin "38") (pinfunction "GPIO34_38") (pintype "bidirectional"))
    )
    (net (code "70") (name "unconnected-(ESP-GPIO46-Pad55)") (class "Default")
      (node (ref "ESP") (pin "55") (pinfunction "GPIO46_55") (pintype "bidirectional"))
    )
    (net (code "71") (name "unconnected-(ESP-MTDI-Pad46)") (class "Default")
      (node (ref "ESP") (pin "46") (pinfunction "MTDI_46") (pintype "bidirectional"))
    )
    (net (code "72") (name "unconnected-(ESP-MTMS-Pad47)") (class "Default")
      (node (ref "ESP") (pin "47") (pinfunction "MTMS_47") (pintype "bidirectional"))
    )
    (net (code "73") (name "unconnected-(ESP-SPICLK-Pad34)") (class "Default")
      (node (ref "ESP") (pin "34") (pinfunction "SPICLK_34") (pintype "bidirectional"))
    )
    (net (code "74") (name "unconnected-(ESP-SPICS0-Pad33)") (class "Default")
      (node (ref "ESP") (pin "33") (pinfunction "SPICS0_33") (pintype "bidirectional"))
    )
    (net (code "75") (name "unconnected-(ESP-SPICS1-Pad29)") (class "Default")
      (node (ref "ESP") (pin "29") (pinfunction "SPICS1_29") (pintype "bidirectional"))
    )
    (net (code "76") (name "unconnected-(ESP-SPID-Pad36)") (class "Default")
      (node (ref "ESP") (pin "36") (pinfunction "SPID_36") (pintype "bidirectional"))
    )
    (net (code "77") (name "unconnected-(ESP-SPIHD-Pad31)") (class "Default")
      (node (ref "ESP") (pin "31") (pinfunction "SPIHD_31") (pintype "bidirectional"))
    )
    (net (code "78") (name "unconnected-(ESP-SPIQ-Pad35)") (class "Default")
      (node (ref "ESP") (pin "35") (pinfunction "SPIQ_35") (pintype "bidirectional"))
    )
    (net (code "79") (name "unconnected-(ESP-SPIWP-Pad32)") (class "Default")
      (node (ref "ESP") (pin "32") (pinfunction "SPIWP_32") (pintype "bidirectional"))
    )
    (net (code "80") (name "unconnected-(ESP-VDD_SPI-Pad30)") (class "Default")
      (node (ref "ESP") (pin "30") (pinfunction "VDD_SPI_30") (pintype "bidirectional"))
    )
    (net (code "81") (name "unconnected-(ESP-XTAL_32K_N-Pad22)") (class "Default")
      (node (ref "ESP") (pin "22") (pinfunction "XTAL_32K_N_22") (pintype "bidirectional"))
    )
    (net (code "82") (name "unconnected-(GPIO0-2-PadP2)") (class "Default")
      (node (ref "GPIO0") (pin "P2") (pinfunction "2_P2") (pintype "bidirectional"))
    )
    (net (code "83") (name "unconnected-(GPIO0-3-PadP3)") (class "Default")
      (node (ref "GPIO0") (pin "P3") (pinfunction "3_P3") (pintype "bidirectional"))
    )
    (net (code "84") (name "unconnected-(L1-CLKO-PadP2)") (class "Default")
      (node (ref "L1") (pin "P2") (pinfunction "CLKO_P2") (pintype "bidirectional"))
    )
    (net (code "85") (name "unconnected-(L1-SDO-PadP3)") (class "Default")
      (node (ref "L1") (pin "P3") (pinfunction "SDO_P3") (pintype "bidirectional"))
    )
    (net (code "86") (name "unconnected-(RESET-2-PadP2)") (class "Default")
      (node (ref "RESET") (pin "P2") (pinfunction "2_P2") (pintype "bidirectional"))
    )
    (net (code "87") (name "unconnected-(RESET-3-PadP3)") (class "Default")
      (node (ref "RESET") (pin "P3") (pinfunction "3_P3") (pintype "bidirectional"))
    )
    (net (code "88") (name "unconnected-(U3-BP-PadP4)") (class "Default")
      (node (ref "U3") (pin "P4") (pinfunction "BP_P4") (pintype "bidirectional"))
    )
    (net (code "89") (name "unconnected-(U4-D3-PadP21)") (class "Default")
      (node (ref "U4") (pin "P21") (pinfunction "D3_P21") (pintype "bidirectional"))
    )
    (net (code "90") (name "unconnected-(U4-D4-PadP22)") (class "Default")
      (node (ref "U4") (pin "P22") (pinfunction "D4_P22") (pintype "bidirectional"))
    )
    (net (code "91") (name "unconnected-(U4-D5-PadP23)") (class "Default")
      (node (ref "U4") (pin "P23") (pinfunction "D5_P23") (pintype "bidirectional"))
    )
    (net (code "92") (name "unconnected-(U4-D6-PadP24)") (class "Default")
      (node (ref "U4") (pin "P24") (pinfunction "D6_P24") (pintype "bidirectional"))
    )
    (net (code "93") (name "unconnected-(U4-D7-PadP25)") (class "Default")
      (node (ref "U4") (pin "P25") (pinfunction "D7_P25") (pintype "bidirectional"))
    )
    (net (code "94") (name "unconnected-(U4-DC{slash}I2C_SA0-PadP15)") (class "Default")
      (node (ref "U4") (pin "P15") (pinfunction "DC/I2C_SA0_P15") (pintype "bidirectional"))
    )
    (net (code "95") (name "unconnected-(U4-E{slash}RD-PadP17)") (class "Default")
      (node (ref "U4") (pin "P17") (pinfunction "E/RD_P17") (pintype "bidirectional"))
    )
    (net (code "96") (name "unconnected-(U4-NC-PadP7)") (class "Default")
      (node (ref "U4") (pin "P7") (pinfunction "NC_P7") (pintype "bidirectional"))
    )
    (net (code "97") (name "unconnected-(U4-R{slash}W-PadP16)") (class "Default")
      (node (ref "U4") (pin "P16") (pinfunction "R/W_P16") (pintype "bidirectional"))
    )
    (net (code "98") (name "unconnected-(U4-{slash}CS-PadP13)") (class "Default")
      (node (ref "U4") (pin "P13") (pinfunction "/CS_P13") (pintype "bidirectional"))
    )
  )
)
